# Lossless_Transmission_Line.net
KiCad netlist of a schematic drawn in Altium Designer
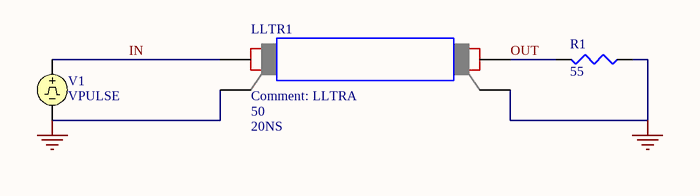
[diagram p0: Lossless Transmission Line.schdoc]

(export (version "E")
  (design (tool "Eeschema 10.0.6"))
  (components
    (comp (ref "LLTR1")
      (value "LLTRA")
      (description "Lossless Transmission Line")
      (fields (field (name "CHAR. IMPEDANCE") "50") (field (name "TRANSMISSION DELAY") "20NS"))
      (libsource (lib "*") (part "LLTRA"))
    )
    (comp (ref "R1") (value "55") (description "Resistor") (libsource (lib "*") (part "RES")))
    (comp (ref "V1")
      (value "VPULSE")
      (description "Pulse Voltage Source")
      (libsource (lib "*") (part "VPULSE"))
    )
  )
  (nets
    (net (code "1") (name "/IN") (class "Default")
      (node (ref "LLTR1") (pin "1") (pinfunction "N1+_1") (pintype "passive"))
      (node (ref "V1") (pin "1") (pinfunction "1_1") (pintype "passive"))
    )
    (net (code "2") (name "/OUT") (class "Default")
      (node (ref "LLTR1") (pin "3") (pinfunction "N2+_3") (pintype "passive"))
      (node (ref "R1") (pin "1") (pinfunction "TOP_1") (pintype "passive"))
    )
    (net (code "3") (name "GND") (class "Default")
      (node (ref "LLTR1") (pin "2") (pinfunction "N1-_2") (pintype "passive"))
      (node (ref "LLTR1") (pin "4") (pinfunction "N2-_4") (pintype "passive"))
      (node (ref "R1") (pin "2") (pinfunction "BOT_2") (pintype "passive"))
      (node (ref "V1") (pin "2") (pinfunction "2_2") (pintype "passive"))
    )
  )
)
